# Z7_DDR3.net
KiCad netlist of a schematic drawn in Altium Designer
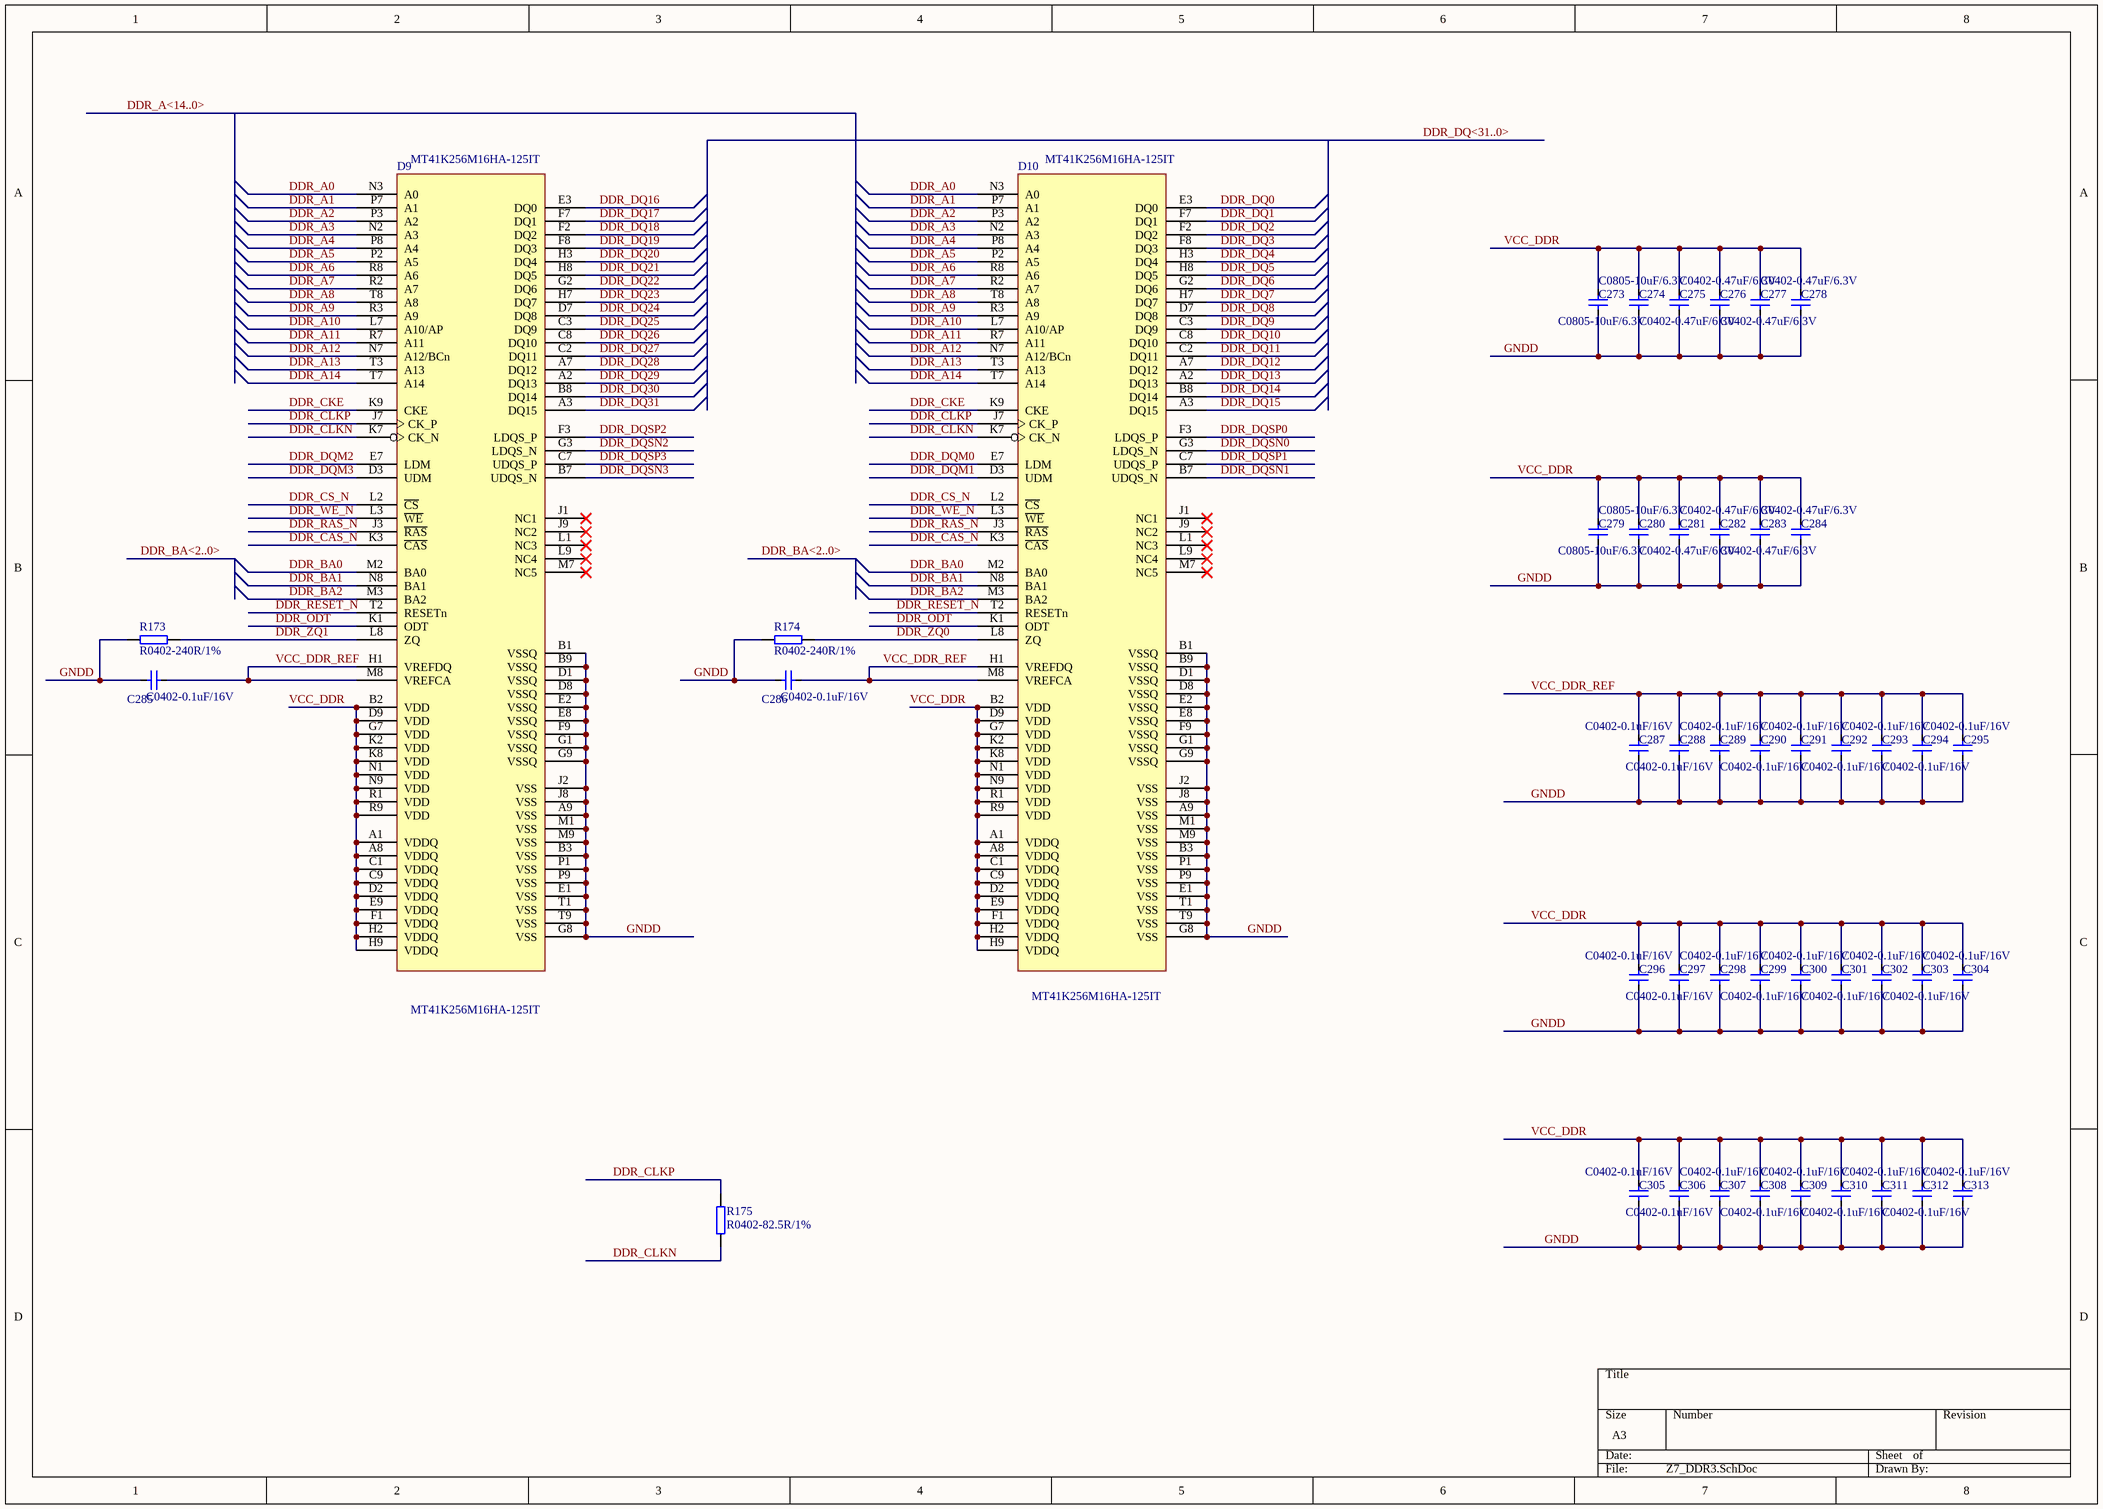
[diagram p0: Z7_DDR3.SchDoc]

(export (version "E")
  (design (tool "Eeschema 10.0.6"))
  (components
    (comp (ref "C273")
      (value "C0805-10uF/6.3V")
      (footprint "C0805")
      (fields (field (name "SCHEMATIC_PART") "CAP"))
      (libsource (lib "Database_Libs1") (part "CAP"))
    )
    (comp (ref "C274")
      (value "C0805-10uF/6.3V")
      (footprint "C0805")
      (fields (field (name "SCHEMATIC_PART") "CAP"))
      (libsource (lib "Database_Libs1") (part "CAP"))
    )
    (comp (ref "C275")
      (value "C0402-0.47uF/6.3V")
      (footprint "C0402")
      (description "X7R")
      (fields (field (name "SCHEMATIC_PART") "CAP") (field (name "MANUFACTURER") "SAMSUNG"))
      (libsource (lib "Database_Libs1") (part "CAP"))
    )
    (comp (ref "C276")
      (value "C0402-0.47uF/6.3V")
      (footprint "C0402")
      (description "X7R")
      (fields (field (name "SCHEMATIC_PART") "CAP") (field (name "MANUFACTURER") "SAMSUNG"))
      (libsource (lib "Database_Libs1") (part "CAP"))
    )
    (comp (ref "C277")
      (value "C0402-0.47uF/6.3V")
      (footprint "C0402")
      (description "X7R")
      (fields (field (name "SCHEMATIC_PART") "CAP") (field (name "MANUFACTURER") "SAMSUNG"))
      (libsource (lib "Database_Libs1") (part "CAP"))
    )
    (comp (ref "C278")
      (value "C0402-0.47uF/6.3V")
      (footprint "C0402")
      (description "X7R")
      (fields (field (name "SCHEMATIC_PART") "CAP") (field (name "MANUFACTURER") "SAMSUNG"))
      (libsource (lib "Database_Libs1") (part "CAP"))
    )
    (comp (ref "C279")
      (value "C0805-10uF/6.3V")
      (footprint "C0805")
      (fields (field (name "SCHEMATIC_PART") "CAP"))
      (libsource (lib "Database_Libs1") (part "CAP"))
    )
    (comp (ref "C280")
      (value "C0805-10uF/6.3V")
      (footprint "C0805")
      (fields (field (name "SCHEMATIC_PART") "CAP"))
      (libsource (lib "Database_Libs1") (part "CAP"))
    )
    (comp (ref "C281")
      (value "C0402-0.47uF/6.3V")
      (footprint "C0402")
      (description "X7R")
      (fields (field (name "SCHEMATIC_PART") "CAP") (field (name "MANUFACTURER") "SAMSUNG"))
      (libsource (lib "Database_Libs1") (part "CAP"))
    )
    (comp (ref "C282")
      (value "C0402-0.47uF/6.3V")
      (footprint "C0402")
      (description "X7R")
      (fields (field (name "SCHEMATIC_PART") "CAP") (field (name "MANUFACTURER") "SAMSUNG"))
      (libsource (lib "Database_Libs1") (part "CAP"))
    )
    (comp (ref "C283")
      (value "C0402-0.47uF/6.3V")
      (footprint "C0402")
      (description "X7R")
      (fields (field (name "SCHEMATIC_PART") "CAP") (field (name "MANUFACTURER") "SAMSUNG"))
      (libsource (lib "Database_Libs1") (part "CAP"))
    )
    (comp (ref "C284")
      (value "C0402-0.47uF/6.3V")
      (footprint "C0402")
      (description "X7R")
      (fields (field (name "SCHEMATIC_PART") "CAP") (field (name "MANUFACTURER") "SAMSUNG"))
      (libsource (lib "Database_Libs1") (part "CAP"))
    )
    (comp (ref "C285")
      (value "C0402-0.1uF/16V")
      (footprint "C0402")
      (description "X7R")
      (fields (field (name "SCHEMATIC_PART") "CAP") (field (name "MANUFACTURER") "SAMSUNG"))
      (libsource (lib "Database_Libs1") (part "CAP"))
    )
    (comp (ref "C286")
      (value "C0402-0.1uF/16V")
      (footprint "C0402")
      (description "X7R")
      (fields (field (name "SCHEMATIC_PART") "CAP") (field (name "MANUFACTURER") "SAMSUNG"))
      (libsource (lib "Database_Libs1") (part "CAP"))
    )
    (comp (ref "C287")
      (value "C0402-0.1uF/16V")
      (footprint "C0402")
      (description "X7R")
      (fields (field (name "SCHEMATIC_PART") "CAP") (field (name "MANUFACTURER") "SAMSUNG"))
      (libsource (lib "Database_Libs1") (part "CAP"))
    )
    (comp (ref "C288")
      (value "C0402-0.1uF/16V")
      (footprint "C0402")
      (description "X7R")
      (fields (field (name "SCHEMATIC_PART") "CAP") (field (name "MANUFACTURER") "SAMSUNG"))
      (libsource (lib "Database_Libs1") (part "CAP"))
    )
    (comp (ref "C289")
      (value "C0402-0.1uF/16V")
      (footprint "C0402")
      (description "X7R")
      (fields (field (name "SCHEMATIC_PART") "CAP") (field (name "MANUFACTURER") "SAMSUNG"))
      (libsource (lib "Database_Libs1") (part "CAP"))
    )
    (comp (ref "C290")
      (value "C0402-0.1uF/16V")
      (footprint "C0402")
      (description "X7R")
      (fields (field (name "SCHEMATIC_PART") "CAP") (field (name "MANUFACTURER") "SAMSUNG"))
      (libsource (lib "Database_Libs1") (part "CAP"))
    )
    (comp (ref "C291")
      (value "C0402-0.1uF/16V")
      (footprint "C0402")
      (description "X7R")
      (fields (field (name "SCHEMATIC_PART") "CAP") (field (name "MANUFACTURER") "SAMSUNG"))
      (libsource (lib "Database_Libs1") (part "CAP"))
    )
    (comp (ref "C292")
      (value "C0402-0.1uF/16V")
      (footprint "C0402")
      (description "X7R")
      (fields (field (name "SCHEMATIC_PART") "CAP") (field (name "MANUFACTURER") "SAMSUNG"))
      (libsource (lib "Database_Libs1") (part "CAP"))
    )
    (comp (ref "C293")
      (value "C0402-0.1uF/16V")
      (footprint "C0402")
      (description "X7R")
      (fields (field (name "SCHEMATIC_PART") "CAP") (field (name "MANUFACTURER") "SAMSUNG"))
      (libsource (lib "Database_Libs1") (part "CAP"))
    )
    (comp (ref "C294")
      (value "C0402-0.1uF/16V")
      (footprint "C0402")
      (description "X7R")
      (fields (field (name "SCHEMATIC_PART") "CAP") (field (name "MANUFACTURER") "SAMSUNG"))
      (libsource (lib "Database_Libs1") (part "CAP"))
    )
    (comp (ref "C295")
      (value "C0402-0.1uF/16V")
      (footprint "C0402")
      (description "X7R")
      (fields (field (name "SCHEMATIC_PART") "CAP") (field (name "MANUFACTURER") "SAMSUNG"))
      (libsource (lib "Database_Libs1") (part "CAP"))
    )
    (comp (ref "C296")
      (value "C0402-0.1uF/16V")
      (footprint "C0402")
      (description "X7R")
      (fields (field (name "SCHEMATIC_PART") "CAP") (field (name "MANUFACTURER") "SAMSUNG"))
      (libsource (lib "Database_Libs1") (part "CAP"))
    )
    (comp (ref "C297")
      (value "C0402-0.1uF/16V")
      (footprint "C0402")
      (description "X7R")
      (fields (field (name "SCHEMATIC_PART") "CAP") (field (name "MANUFACTURER") "SAMSUNG"))
      (libsource (lib "Database_Libs1") (part "CAP"))
    )
    (comp (ref "C298")
      (value "C0402-0.1uF/16V")
      (footprint "C0402")
      (description "X7R")
      (fields (field (name "SCHEMATIC_PART") "CAP") (field (name "MANUFACTURER") "SAMSUNG"))
      (libsource (lib "Database_Libs1") (part "CAP"))
    )
    (comp (ref "C299")
      (value "C0402-0.1uF/16V")
      (footprint "C0402")
      (description "X7R")
      (fields (field (name "SCHEMATIC_PART") "CAP") (field (name "MANUFACTURER") "SAMSUNG"))
      (libsource (lib "Database_Libs1") (part "CAP"))
    )
    (comp (ref "C300")
      (value "C0402-0.1uF/16V")
      (footprint "C0402")
      (description "X7R")
      (fields (field (name "SCHEMATIC_PART") "CAP") (field (name "MANUFACTURER") "SAMSUNG"))
      (libsource (lib "Database_Libs1") (part "CAP"))
    )
    (comp (ref "C301")
      (value "C0402-0.1uF/16V")
      (footprint "C0402")
      (description "X7R")
      (fields (field (name "SCHEMATIC_PART") "CAP") (field (name "MANUFACTURER") "SAMSUNG"))
      (libsource (lib "Database_Libs1") (part "CAP"))
    )
    (comp (ref "C302")
      (value "C0402-0.1uF/16V")
      (footprint "C0402")
      (description "X7R")
      (fields (field (name "SCHEMATIC_PART") "CAP") (field (name "MANUFACTURER") "SAMSUNG"))
      (libsource (lib "Database_Libs1") (part "CAP"))
    )
    (comp (ref "C303")
      (value "C0402-0.1uF/16V")
      (footprint "C0402")
      (description "X7R")
      (fields (field (name "SCHEMATIC_PART") "CAP") (field (name "MANUFACTURER") "SAMSUNG"))
      (libsource (lib "Database_Libs1") (part "CAP"))
    )
    (comp (ref "C304")
      (value "C0402-0.1uF/16V")
      (footprint "C0402")
      (description "X7R")
      (fields (field (name "SCHEMATIC_PART") "CAP") (field (name "MANUFACTURER") "SAMSUNG"))
      (libsource (lib "Database_Libs1") (part "CAP"))
    )
    (comp (ref "C305")
      (value "C0402-0.1uF/16V")
      (footprint "C0402")
      (description "X7R")
      (fields (field (name "SCHEMATIC_PART") "CAP") (field (name "MANUFACTURER") "SAMSUNG"))
      (libsource (lib "Database_Libs1") (part "CAP"))
    )
    (comp (ref "C306")
      (value "C0402-0.1uF/16V")
      (footprint "C0402")
      (description "X7R")
      (fields (field (name "SCHEMATIC_PART") "CAP") (field (name "MANUFACTURER") "SAMSUNG"))
      (libsource (lib "Database_Libs1") (part "CAP"))
    )
    (comp (ref "C307")
      (value "C0402-0.1uF/16V")
      (footprint "C0402")
      (description "X7R")
      (fields (field (name "SCHEMATIC_PART") "CAP") (field (name "MANUFACTURER") "SAMSUNG"))
      (libsource (lib "Database_Libs1") (part "CAP"))
    )
    (comp (ref "C308")
      (value "C0402-0.1uF/16V")
      (footprint "C0402")
      (description "X7R")
      (fields (field (name "SCHEMATIC_PART") "CAP") (field (name "MANUFACTURER") "SAMSUNG"))
      (libsource (lib "Database_Libs1") (part "CAP"))
    )
    (comp (ref "C309")
      (value "C0402-0.1uF/16V")
      (footprint "C0402")
      (description "X7R")
      (fields (field (name "SCHEMATIC_PART") "CAP") (field (name "MANUFACTURER") "SAMSUNG"))
      (libsource (lib "Database_Libs1") (part "CAP"))
    )
    (comp (ref "C310")
      (value "C0402-0.1uF/16V")
      (footprint "C0402")
      (description "X7R")
      (fields (field (name "SCHEMATIC_PART") "CAP") (field (name "MANUFACTURER") "SAMSUNG"))
      (libsource (lib "Database_Libs1") (part "CAP"))
    )
    (comp (ref "C311")
      (value "C0402-0.1uF/16V")
      (footprint "C0402")
      (description "X7R")
      (fields (field (name "SCHEMATIC_PART") "CAP") (field (name "MANUFACTURER") "SAMSUNG"))
      (libsource (lib "Database_Libs1") (part "CAP"))
    )
    (comp (ref "C312")
      (value "C0402-0.1uF/16V")
      (footprint "C0402")
      (description "X7R")
      (fields (field (name "SCHEMATIC_PART") "CAP") (field (name "MANUFACTURER") "SAMSUNG"))
      (libsource (lib "Database_Libs1") (part "CAP"))
    )
    (comp (ref "C313")
      (value "C0402-0.1uF/16V")
      (footprint "C0402")
      (description "X7R")
      (fields (field (name "SCHEMATIC_PART") "CAP") (field (name "MANUFACTURER") "SAMSUNG"))
      (libsource (lib "Database_Libs1") (part "CAP"))
    )
    (comp (ref "D9")
      (value "MT41K256M16HA-125IT")
      (footprint "BGA96C80P16X9_1400X900X120")
      (fields (field (name "PART_NUMBER") "MT41K256M16HA-125IT"))
      (libsource (lib "SCHLIB1") (part "MT41K256M16"))
    )
    (comp (ref "D10")
      (value "MT41K256M16HA-125IT")
      (footprint "BGA96C80P16X9_1400X900X120")
      (fields (field (name "PART_NUMBER") "MT41K256M16HA-125IT"))
      (libsource (lib "SCHLIB1") (part "MT41K256M16"))
    )
    (comp (ref "R173")
      (value "R0402-240R/1%")
      (footprint "R0402")
      (fields (field (name "SCHEMATIC_PART") "RES") (field (name "MANUFACTURER") "SAMSUNG"))
      (libsource (lib "Database_Libs1") (part "RES"))
    )
    (comp (ref "R174")
      (value "R0402-240R/1%")
      (footprint "R0402")
      (fields (field (name "SCHEMATIC_PART") "RES") (field (name "MANUFACTURER") "SAMSUNG"))
      (libsource (lib "Database_Libs1") (part "RES"))
    )
    (comp (ref "R175")
      (value "R0402-82.5R/1%")
      (footprint "R0402")
      (fields (field (name "SCHEMATIC_PART") "RES") (field (name "MANUFACTURER") "SAMSUNG"))
      (libsource (lib "Database_Libs1") (part "RES"))
    )
  )
  (nets
    (net (code "4") (name "/DDR_A0") (class "Default")
      (node (ref "D10") (pin "N3") (pinfunction "A0_N3") (pintype "passive"))
      (node (ref "D9") (pin "N3") (pinfunction "A0_N3") (pintype "passive"))
    )
    (net (code "5") (name "/DDR_A1") (class "Default")
      (node (ref "D10") (pin "P7") (pinfunction "A1_P7") (pintype "passive"))
      (node (ref "D9") (pin "P7") (pinfunction "A1_P7") (pintype "passive"))
    )
    (net (code "6") (name "/DDR_A2") (class "Default")
      (node (ref "D10") (pin "P3") (pinfunction "A2_P3") (pintype "passive"))
      (node (ref "D9") (pin "P3") (pinfunction "A2_P3") (pintype "passive"))
    )
    (net (code "7") (name "/DDR_A3") (class "Default")
      (node (ref "D10") (pin "N2") (pinfunction "A3_N2") (pintype "passive"))
      (node (ref "D9") (pin "N2") (pinfunction "A3_N2") (pintype "passive"))
    )
    (net (code "8") (name "/DDR_A4") (class "Default")
      (node (ref "D10") (pin "P8") (pinfunction "A4_P8") (pintype "passive"))
      (node (ref "D9") (pin "P8") (pinfunction "A4_P8") (pintype "passive"))
    )
    (net (code "9") (name "/DDR_A5") (class "Default")
      (node (ref "D10") (pin "P2") (pinfunction "A5_P2") (pintype "passive"))
      (node (ref "D9") (pin "P2") (pinfunction "A5_P2") (pintype "passive"))
    )
    (net (code "10") (name "/DDR_A6") (class "Default")
      (node (ref "D10") (pin "R8") (pinfunction "A6_R8") (pintype "passive"))
      (node (ref "D9") (pin "R8") (pinfunction "A6_R8") (pintype "passive"))
    )
    (net (code "11") (name "/DDR_A7") (class "Default")
      (node (ref "D10") (pin "R2") (pinfunction "A7_R2") (pintype "passive"))
      (node (ref "D9") (pin "R2") (pinfunction "A7_R2") (pintype "passive"))
    )
    (net (code "12") (name "/DDR_A8") (class "Default")
      (node (ref "D10") (pin "T8") (pinfunction "A8_T8") (pintype "passive"))
      (node (ref "D9") (pin "T8") (pinfunction "A8_T8") (pintype "passive"))
    )
    (net (code "13") (name "/DDR_A9") (class "Default")
      (node (ref "D10") (pin "R3") (pinfunction "A9_R3") (pintype "passive"))
      (node (ref "D9") (pin "R3") (pinfunction "A9_R3") (pintype "passive"))
    )
    (net (code "14") (name "/DDR_A10") (class "Default")
      (node (ref "D10") (pin "L7") (pinfunction "A10/AP_L7") (pintype "passive"))
      (node (ref "D9") (pin "L7") (pinfunction "A10/AP_L7") (pintype "passive"))
    )
    (net (code "15") (name "/DDR_A11") (class "Default")
      (node (ref "D10") (pin "R7") (pinfunction "A11_R7") (pintype "passive"))
      (node (ref "D9") (pin "R7") (pinfunction "A11_R7") (pintype "passive"))
    )
    (net (code "16") (name "/DDR_A12") (class "Default")
      (node (ref "D10") (pin "N7") (pinfunction "A12/BCn_N7") (pintype "passive"))
      (node (ref "D9") (pin "N7") (pinfunction "A12/BCn_N7") (pintype "passive"))
    )
    (net (code "17") (name "/DDR_A13") (class "Default")
      (node (ref "D10") (pin "T3") (pinfunction "A13_T3") (pintype "passive"))
      (node (ref "D9") (pin "T3") (pinfunction "A13_T3") (pintype "passive"))
    )
    (net (code "18") (name "/DDR_A14") (class "Default")
      (node (ref "D10") (pin "T7") (pinfunction "A14_T7") (pintype "passive"))
      (node (ref "D9") (pin "T7") (pinfunction "A14_T7") (pintype "passive"))
    )
    (net (code "19") (name "/DDR_BA0") (class "Default")
      (node (ref "D10") (pin "M2") (pinfunction "BA0_M2") (pintype "passive"))
      (node (ref "D9") (pin "M2") (pinfunction "BA0_M2") (pintype "passive"))
    )
    (net (code "20") (name "/DDR_BA1") (class "Default")
      (node (ref "D10") (pin "N8") (pinfunction "BA1_N8") (pintype "passive"))
      (node (ref "D9") (pin "N8") (pinfunction "BA1_N8") (pintype "passive"))
    )
    (net (code "21") (name "/DDR_BA2") (class "Default")
      (node (ref "D10") (pin "M3") (pinfunction "BA2_M3") (pintype "passive"))
      (node (ref "D9") (pin "M3") (pinfunction "BA2_M3") (pintype "passive"))
    )
    (net (code "22") (name "/DDR_CAS_N") (class "Default")
      (node (ref "D10") (pin "K3") (pinfunction "~{CAS}_K3") (pintype "passive"))
      (node (ref "D9") (pin "K3") (pinfunction "~{CAS}_K3") (pintype "passive"))
    )
    (net (code "23") (name "/DDR_CKE") (class "Default")
      (node (ref "D10") (pin "K9") (pinfunction "CKE_K9") (pintype "passive"))
      (node (ref "D9") (pin "K9") (pinfunction "CKE_K9") (pintype "passive"))
    )
    (net (code "24") (name "/DDR_CLKN") (class "Default")
      (node (ref "D10") (pin "K7") (pinfunction "CK_N_K7") (pintype "passive"))
      (node (ref "D9") (pin "K7") (pinfunction "CK_N_K7") (pintype "passive"))
      (node (ref "R175") (pin "1") (pintype "passive"))
    )
    (net (code "25") (name "/DDR_CLKP") (class "Default")
      (node (ref "D10") (pin "J7") (pinfunction "CK_P_J7") (pintype "passive"))
      (node (ref "D9") (pin "J7") (pinfunction "CK_P_J7") (pintype "passive"))
      (node (ref "R175") (pin "2") (pintype "passive"))
    )
    (net (code "26") (name "/DDR_CS_N") (class "Default")
      (node (ref "D10") (pin "L2") (pinfunction "~{CS}_L2") (pintype "passive"))
      (node (ref "D9") (pin "L2") (pinfunction "~{CS}_L2") (pintype "passive"))
    )
    (net (code "27") (name "/DDR_DQ0") (class "Default")
      (node (ref "D10") (pin "E3") (pinfunction "DQ0_E3") (pintype "passive"))
    )
    (net (code "28") (name "/DDR_DQ1") (class "Default")
      (node (ref "D10") (pin "F7") (pinfunction "DQ1_F7") (pintype "passive"))
    )
    (net (code "29") (name "/DDR_DQ2") (class "Default")
      (node (ref "D10") (pin "F2") (pinfunction "DQ2_F2") (pintype "passive"))
    )
    (net (code "30") (name "/DDR_DQ3") (class "Default")
      (node (ref "D10") (pin "F8") (pinfunction "DQ3_F8") (pintype "passive"))
    )
    (net (code "31") (name "/DDR_DQ4") (class "Default")
      (node (ref "D10") (pin "H3") (pinfunction "DQ4_H3") (pintype "passive"))
    )
    (net (code "32") (name "/DDR_DQ5") (class "Default")
      (node (ref "D10") (pin "H8") (pinfunction "DQ5_H8") (pintype "passive"))
    )
    (net (code "33") (name "/DDR_DQ6") (class "Default")
      (node (ref "D10") (pin "G2") (pinfunction "DQ6_G2") (pintype "passive"))
    )
    (net (code "34") (name "/DDR_DQ7") (class "Default")
      (node (ref "D10") (pin "H7") (pinfunction "DQ7_H7") (pintype "passive"))
    )
    (net (code "35") (name "/DDR_DQ8") (class "Default")
      (node (ref "D10") (pin "D7") (pinfunction "DQ8_D7") (pintype "passive"))
    )
    (net (code "36") (name "/DDR_DQ9") (class "Default")
      (node (ref "D10") (pin "C3") (pinfunction "DQ9_C3") (pintype "passive"))
    )
    (net (code "37") (name "/DDR_DQ10") (class "Default")
      (node (ref "D10") (pin "C8") (pinfunction "DQ10_C8") (pintype "passive"))
    )
    (net (code "38") (name "/DDR_DQ11") (class "Default")
      (node (ref "D10") (pin "C2") (pinfunction "DQ11_C2") (pintype "passive"))
    )
    (net (code "39") (name "/DDR_DQ12") (class "Default")
      (node (ref "D10") (pin "A7") (pinfunction "DQ12_A7") (pintype "passive"))
    )
    (net (code "40") (name "/DDR_DQ13") (class "Default")
      (node (ref "D10") (pin "A2") (pinfunction "DQ13_A2") (pintype "passive"))
    )
    (net (code "41") (name "/DDR_DQ14") (class "Default")
      (node (ref "D10") (pin "B8") (pinfunction "DQ14_B8") (pintype "passive"))
    )
    (net (code "42") (name "/DDR_DQ15") (class "Default")
      (node (ref "D10") (pin "A3") (pinfunction "DQ15_A3") (pintype "passive"))
    )
    (net (code "43") (name "/DDR_DQ16") (class "Default")
      (node (ref "D9") (pin "E3") (pinfunction "DQ0_E3") (pintype "passive"))
    )
    (net (code "44") (name "/DDR_DQ17") (class "Default")
      (node (ref "D9") (pin "F7") (pinfunction "DQ1_F7") (pintype "passive"))
    )
    (net (code "45") (name "/DDR_DQ18") (class "Default")
      (node (ref "D9") (pin "F2") (pinfunction "DQ2_F2") (pintype "passive"))
    )
    (net (code "46") (name "/DDR_DQ19") (class "Default")
      (node (ref "D9") (pin "F8") (pinfunction "DQ3_F8") (pintype "passive"))
    )
    (net (code "47") (name "/DDR_DQ20") (class "Default")
      (node (ref "D9") (pin "H3") (pinfunction "DQ4_H3") (pintype "passive"))
    )
    (net (code "48") (name "/DDR_DQ21") (class "Default")
      (node (ref "D9") (pin "H8") (pinfunction "DQ5_H8") (pintype "passive"))
    )
    (net (code "49") (name "/DDR_DQ22") (class "Default")
      (node (ref "D9") (pin "G2") (pinfunction "DQ6_G2") (pintype "passive"))
    )
    (net (code "50") (name "/DDR_DQ23") (class "Default")
      (node (ref "D9") (pin "H7") (pinfunction "DQ7_H7") (pintype "passive"))
    )
    (net (code "51") (name "/DDR_DQ24") (class "Default")
      (node (ref "D9") (pin "D7") (pinfunction "DQ8_D7") (pintype "passive"))
    )
    (net (code "52") (name "/DDR_DQ25") (class "Default")
      (node (ref "D9") (pin "C3") (pinfunction "DQ9_C3") (pintype "passive"))
    )
    (net (code "53") (name "/DDR_DQ26") (class "Default")
      (node (ref "D9") (pin "C8") (pinfunction "DQ10_C8") (pintype "passive"))
    )
    (net (code "54") (name "/DDR_DQ27") (class "Default")
      (node (ref "D9") (pin "C2") (pinfunction "DQ11_C2") (pintype "passive"))
    )
    (net (code "55") (name "/DDR_DQ28") (class "Default")
      (node (ref "D9") (pin "A7") (pinfunction "DQ12_A7") (pintype "passive"))
    )
    (net (code "56") (name "/DDR_DQ29") (class "Default")
      (node (ref "D9") (pin "A2") (pinfunction "DQ13_A2") (pintype "passive"))
    )
    (net (code "57") (name "/DDR_DQ30") (class "Default")
      (node (ref "D9") (pin "B8") (pinfunction "DQ14_B8") (pintype "passive"))
    )
    (net (code "58") (name "/DDR_DQ31") (class "Default")
      (node (ref "D9") (pin "A3") (pinfunction "DQ15_A3") (pintype "passive"))
    )
    (net (code "59") (name "/DDR_DQM0") (class "Default")
      (node (ref "D10") (pin "E7") (pinfunction "LDM_E7") (pintype "passive"))
    )
    (net (code "60") (name "/DDR_DQM1") (class "Default")
      (node (ref "D10") (pin "D3") (pinfunction "UDM_D3") (pintype "passive"))
    )
    (net (code "61") (name "/DDR_DQM2") (class "Default")
      (node (ref "D9") (pin "E7") (pinfunction "LDM_E7") (pintype "passive"))
    )
    (net (code "62") (name "/DDR_DQM3") (class "Default")
      (node (ref "D9") (pin "D3") (pinfunction "UDM_D3") (pintype "passive"))
    )
    (net (code "63") (name "/DDR_DQSN0") (class "Default")
      (node (ref "D10") (pin "G3") (pinfunction "LDQS_N_G3") (pintype "passive"))
    )
    (net (code "64") (name "/DDR_DQSN1") (class "Default")
      (node (ref "D10") (pin "B7") (pinfunction "UDQS_N_B7") (pintype "passive"))
    )
    (net (code "65") (name "/DDR_DQSN2") (class "Default")
      (node (ref "D9") (pin "G3") (pinfunction "LDQS_N_G3") (pintype "passive"))
    )
    (net (code "66") (name "/DDR_DQSN3") (class "Default")
      (node (ref "D9") (pin "B7") (pinfunction "UDQS_N_B7") (pintype "passive"))
    )
    (net (code "67") (name "/DDR_DQSP0") (class "Default")
      (node (ref "D10") (pin "F3") (pinfunction "LDQS_P_F3") (pintype "passive"))
    )
    (net (code "68") (name "/DDR_DQSP1") (class "Default")
      (node (ref "D10") (pin "C7") (pinfunction "UDQS_P_C7") (pintype "passive"))
    )
    (net (code "69") (name "/DDR_DQSP2") (class "Default")
      (node (ref "D9") (pin "F3") (pinfunction "LDQS_P_F3") (pintype "passive"))
    )
    (net (code "70") (name "/DDR_DQSP3") (class "Default")
      (node (ref "D9") (pin "C7") (pinfunction "UDQS_P_C7") (pintype "passive"))
    )
    (net (code "71") (name "/DDR_ODT") (class "Default")
      (node (ref "D10") (pin "K1") (pinfunction "ODT_K1") (pintype "passive"))
      (node (ref "D9") (pin "K1") (pinfunction "ODT_K1") (pintype "passive"))
    )
    (net (code "72") (name "/DDR_RAS_N") (class "Default")
      (node (ref "D10") (pin "J3") (pinfunction "~{RAS}_J3") (pintype "passive"))
      (node (ref "D9") (pin "J3") (pinfunction "~{RAS}_J3") (pintype "passive"))
    )
    (net (code "73") (name "/DDR_RESET_N") (class "Default")
      (node (ref "D10") (pin "T2") (pinfunction "RESETn_T2") (pintype "passive"))
      (node (ref "D9") (pin "T2") (pinfunction "RESETn_T2") (pintype "passive"))
    )
    (net (code "74") (name "/DDR_WE_N") (class "Default")
      (node (ref "D10") (pin "L3") (pinfunction "~{WE}_L3") (pintype "passive"))
      (node (ref "D9") (pin "L3") (pinfunction "~{WE}_L3") (pintype "passive"))
    )
    (net (code "75") (name "/DDR_ZQ0") (class "Default")
      (node (ref "D10") (pin "L8") (pinfunction "ZQ_L8") (pintype "passive"))
      (node (ref "R174") (pin "1") (pintype "passive"))
    )
    (net (code "76") (name "/DDR_ZQ1") (class "Default")
      (node (ref "D9") (pin "L8") (pinfunction "ZQ_L8") (pintype "passive"))
      (node (ref "R173") (pin "1") (pintype "passive"))
    )
    (net (code "77") (name "/GNDD") (class "Default")
      (node (ref "C273") (pin "2") (pinfunction "2_2") (pintype "passive"))
      (node (ref "C274") (pin "2") (pinfunction "2_2") (pintype "passive"))
      (node (ref "C275") (pin "2") (pinfunction "2_2") (pintype "passive"))
      (node (ref "C276") (pin "2") (pinfunction "2_2") (pintype "passive"))
      (node (ref "C277") (pin "2") (pinfunction "2_2") (pintype "passive"))
      (node (ref "C278") (pin "2") (pinfunction "2_2") (pintype "passive"))
      (node (ref "C279") (pin "2") (pinfunction "2_2") (pintype "passive"))
      (node (ref "C280") (pin "2") (pinfunction "2_2") (pintype "passive"))
      (node (ref "C281") (pin "2") (pinfunction "2_2") (pintype "passive"))
      (node (ref "C282") (pin "2") (pinfunction "2_2") (pintype "passive"))
      (node (ref "C283") (pin "2") (pinfunction "2_2") (pintype "passive"))
      (node (ref "C284") (pin "2") (pinfunction "2_2") (pintype "passive"))
      (node (ref "C285") (pin "1") (pinfunction "1_1") (pintype "passive"))
      (node (ref "C286") (pin "1") (pinfunction "1_1") (pintype "passive"))
      (node (ref "C287") (pin "2") (pinfunction "2_2") (pintype "passive"))
      (node (ref "C288") (pin "2") (pinfunction "2_2") (pintype "passive"))
      (node (ref "C289") (pin "2") (pinfunction "2_2") (pintype "passive"))
      (node (ref "C290") (pin "2") (pinfunction "2_2") (pintype "passive"))
      (node (ref "C291") (pin "2") (pinfunction "2_2") (pintype "passive"))
      (node (ref "C292") (pin "2") (pinfunction "2_2") (pintype "passive"))
      (node (ref "C293") (pin "2") (pinfunction "2_2") (pintype "passive"))
      (node (ref "C294") (pin "2") (pinfunction "2_2") (pintype "passive"))
      (node (ref "C295") (pin "2") (pinfunction "2_2") (pintype "passive"))
      (node (ref "C296") (pin "2") (pinfunction "2_2") (pintype "passive"))
      (node (ref "C297") (pin "2") (pinfunction "2_2") (pintype "passive"))
      (node (ref "C298") (pin "2") (pinfunction "2_2") (pintype "passive"))
      (node (ref "C299") (pin "2") (pinfunction "2_2") (pintype "passive"))
      (node (ref "C300") (pin "2") (pinfunction "2_2") (pintype "passive"))
      (node (ref "C301") (pin "2") (pinfunction "2_2") (pintype "passive"))
      (node (ref "C302") (pin "2") (pinfunction "2_2") (pintype "passive"))
      (node (ref "C303") (pin "2") (pinfunction "2_2") (pintype "passive"))
      (node (ref "C304") (pin "2") (pinfunction "2_2") (pintype "passive"))
      (node (ref "C305") (pin "2") (pinfunction "2_2") (pintype "passive"))
      (node (ref "C306") (pin "2") (pinfunction "2_2") (pintype "passive"))
      (node (ref "C307") (pin "2") (pinfunction "2_2") (pintype "passive"))
      (node (ref "C308") (pin "2") (pinfunction "2_2") (pintype "passive"))
      (node (ref "C309") (pin "2") (pinfunction "2_2") (pintype "passive"))
      (node (ref "C310") (pin "2") (pinfunction "2_2") (pintype "passive"))
      (node (ref "C311") (pin "2") (pinfunction "2_2") (pintype "passive"))
      (node (ref "C312") (pin "2") (pinfunction "2_2") (pintype "passive"))
      (node (ref "C313") (pin "2") (pinfunction "2_2") (pintype "passive"))
      (node (ref "D10") (pin "A9") (pinfunction "VSS_A9") (pintype "passive"))
      (node (ref "D10") (pin "B1") (pinfunction "VSSQ_B1") (pintype "passive"))
      (node (ref "D10") (pin "B3") (pinfunction "VSS_B3") (pintype "passive"))
      (node (ref "D10") (pin "B9") (pinfunction "VSSQ_B9") (pintype "passive"))
      (node (ref "D10") (pin "D1") (pinfunction "VSSQ_D1") (pintype "passive"))
      (node (ref "D10") (pin "D8") (pinfunction "VSSQ_D8") (pintype "passive"))
      (node (ref "D10") (pin "E1") (pinfunction "VSS_E1") (pintype "passive"))
      (node (ref "D10") (pin "E2") (pinfunction "VSSQ_E2") (pintype "passive"))
      (node (ref "D10") (pin "E8") (pinfunction "VSSQ_E8") (pintype "passive"))
      (node (ref "D10") (pin "F9") (pinfunction "VSSQ_F9") (pintype "passive"))
      (node (ref "D10") (pin "G1") (pinfunction "VSSQ_G1") (pintype "passive"))
      (node (ref "D10") (pin "G8") (pinfunction "VSS_G8") (pintype "passive"))
      (node (ref "D10") (pin "G9") (pinfunction "VSSQ_G9") (pintype "passive"))
      (node (ref "D10") (pin "J2") (pinfunction "VSS_J2") (pintype "passive"))
      (node (ref "D10") (pin "J8") (pinfunction "VSS_J8") (pintype "passive"))
      (node (ref "D10") (pin "M1") (pinfunction "VSS_M1") (pintype "passive"))
      (node (ref "D10") (pin "M9") (pinfunction "VSS_M9") (pintype "passive"))
      (node (ref "D10") (pin "P1") (pinfunction "VSS_P1") (pintype "passive"))
      (node (ref "D10") (pin "P9") (pinfunction "VSS_P9") (pintype "passive"))
      (node (ref "D10") (pin "T1") (pinfunction "VSS_T1") (pintype "passive"))
      (node (ref "D10") (pin "T9") (pinfunction "VSS_T9") (pintype "passive"))
      (node (ref "D9") (pin "A9") (pinfunction "VSS_A9") (pintype "passive"))
      (node (ref "D9") (pin "B1") (pinfunction "VSSQ_B1") (pintype "passive"))
      (node (ref "D9") (pin "B3") (pinfunction "VSS_B3") (pintype "passive"))
      (node (ref "D9") (pin "B9") (pinfunction "VSSQ_B9") (pintype "passive"))
      (node (ref "D9") (pin "D1") (pinfunction "VSSQ_D1") (pintype "passive"))
      (node (ref "D9") (pin "D8") (pinfunction "VSSQ_D8") (pintype "passive"))
      (node (ref "D9") (pin "E1") (pinfunction "VSS_E1") (pintype "passive"))
      (node (ref "D9") (pin "E2") (pinfunction "VSSQ_E2") (pintype "passive"))
      (node (ref "D9") (pin "E8") (pinfunction "VSSQ_E8") (pintype "passive"))
      (node (ref "D9") (pin "F9") (pinfunction "VSSQ_F9") (pintype "passive"))
      (node (ref "D9") (pin "G1") (pinfunction "VSSQ_G1") (pintype "passive"))
      (node (ref "D9") (pin "G8") (pinfunction "VSS_G8") (pintype "passive"))
      (node (ref "D9") (pin "G9") (pinfunction "VSSQ_G9") (pintype "passive"))
      (node (ref "D9") (pin "J2") (pinfunction "VSS_J2") (pintype "passive"))
      (node (ref "D9") (pin "J8") (pinfunction "VSS_J8") (pintype "passive"))
      (node (ref "D9") (pin "M1") (pinfunction "VSS_M1") (pintype "passive"))
      (node (ref "D9") (pin "M9") (pinfunction "VSS_M9") (pintype "passive"))
      (node (ref "D9") (pin "P1") (pinfunction "VSS_P1") (pintype "passive"))
      (node (ref "D9") (pin "P9") (pinfunction "VSS_P9") (pintype "passive"))
      (node (ref "D9") (pin "T1") (pinfunction "VSS_T1") (pintype "passive"))
      (node (ref "D9") (pin "T9") (pinfunction "VSS_T9") (pintype "passive"))
      (node (ref "R173") (pin "2") (pintype "passive"))
      (node (ref "R174") (pin "2") (pintype "passive"))
    )
    (net (code "78") (name "/VCC_DDR") (class "Default")
      (node (ref "C273") (pin "1") (pinfunction "1_1") (pintype "passive"))
      (node (ref "C274") (pin "1") (pinfunction "1_1") (pintype "passive"))
      (node (ref "C275") (pin "1") (pinfunction "1_1") (pintype "passive"))
      (node (ref "C276") (pin "1") (pinfunction "1_1") (pintype "passive"))
      (node (ref "C277") (pin "1") (pinfunction "1_1") (pintype "passive"))
      (node (ref "C278") (pin "1") (pinfunction "1_1") (pintype "passive"))
      (node (ref "C279") (pin "1") (pinfunction "1_1") (pintype "passive"))
      (node (ref "C280") (pin "1") (pinfunction "1_1") (pintype "passive"))
      (node (ref "C281") (pin "1") (pinfunction "1_1") (pintype "passive"))
      (node (ref "C282") (pin "1") (pinfunction "1_1") (pintype "passive"))
      (node (ref "C283") (pin "1") (pinfunction "1_1") (pintype "passive"))
      (node (ref "C284") (pin "1") (pinfunction "1_1") (pintype "passive"))
      (node (ref "C296") (pin "1") (pinfunction "1_1") (pintype "passive"))
      (node (ref "C297") (pin "1") (pinfunction "1_1") (pintype "passive"))
      (node (ref "C298") (pin "1") (pinfunction "1_1") (pintype "passive"))
      (node (ref "C299") (pin "1") (pinfunction "1_1") (pintype "passive"))
      (node (ref "C300") (pin "1") (pinfunction "1_1") (pintype "passive"))
      (node (ref "C301") (pin "1") (pinfunction "1_1") (pintype "passive"))
      (node (ref "C302") (pin "1") (pinfunction "1_1") (pintype "passive"))
      (node (ref "C303") (pin "1") (pinfunction "1_1") (pintype "passive"))
      (node (ref "C304") (pin "1") (pinfunction "1_1") (pintype "passive"))
      (node (ref "C305") (pin "1") (pinfunction "1_1") (pintype "passive"))
      (node (ref "C306") (pin "1") (pinfunction "1_1") (pintype "passive"))
      (node (ref "C307") (pin "1") (pinfunction "1_1") (pintype "passive"))
      (node (ref "C308") (pin "1") (pinfunction "1_1") (pintype "passive"))
      (node (ref "C309") (pin "1") (pinfunction "1_1") (pintype "passive"))
      (node (ref "C310") (pin "1") (pinfunction "1_1") (pintype "passive"))
      (node (ref "C311") (pin "1") (pinfunction "1_1") (pintype "passive"))
      (node (ref "C312") (pin "1") (pinfunction "1_1") (pintype "passive"))
      (node (ref "C313") (pin "1") (pinfunction "1_1") (pintype "passive"))
      (node (ref "D10") (pin "A1") (pinfunction "VDDQ_A1") (pintype "passive"))
      (node (ref "D10") (pin "A8") (pinfunction "VDDQ_A8") (pintype "passive"))
      (node (ref "D10") (pin "B2") (pinfunction "VDD_B2") (pintype "passive"))
      (node (ref "D10") (pin "C1") (pinfunction "VDDQ_C1") (pintype "passive"))
      (node (ref "D10") (pin "C9") (pinfunction "VDDQ_C9") (pintype "passive"))
      (node (ref "D10") (pin "D2") (pinfunction "VDDQ_D2") (pintype "passive"))
      (node (ref "D10") (pin "D9") (pinfunction "VDD_D9") (pintype "passive"))
      (node (ref "D10") (pin "E9") (pinfunction "VDDQ_E9") (pintype "passive"))
      (node (ref "D10") (pin "F1") (pinfunction "VDDQ_F1") (pintype "passive"))
      (node (ref "D10") (pin "G7") (pinfunction "VDD_G7") (pintype "passive"))
      (node (ref "D10") (pin "H2") (pinfunction "VDDQ_H2") (pintype "passive"))
      (node (ref "D10") (pin "H9") (pinfunction "VDDQ_H9") (pintype "passive"))
      (node (ref "D10") (pin "K2") (pinfunction "VDD_K2") (pintype "passive"))
      (node (ref "D10") (pin "K8") (pinfunction "VDD_K8") (pintype "passive"))
      (node (ref "D10") (pin "N1") (pinfunction "VDD_N1") (pintype "passive"))
      (node (ref "D10") (pin "N9") (pinfunction "VDD_N9") (pintype "passive"))
      (node (ref "D10") (pin "R1") (pinfunction "VDD_R1") (pintype "passive"))
      (node (ref "D10") (pin "R9") (pinfunction "VDD_R9") (pintype "passive"))
      (node (ref "D9") (pin "A1") (pinfunction "VDDQ_A1") (pintype "passive"))
      (node (ref "D9") (pin "A8") (pinfunction "VDDQ_A8") (pintype "passive"))
      (node (ref "D9") (pin "B2") (pinfunction "VDD_B2") (pintype "passive"))
      (node (ref "D9") (pin "C1") (pinfunction "VDDQ_C1") (pintype "passive"))
      (node (ref "D9") (pin "C9") (pinfunction "VDDQ_C9") (pintype "passive"))
      (node (ref "D9") (pin "D2") (pinfunction "VDDQ_D2") (pintype "passive"))
      (node (ref "D9") (pin "D9") (pinfunction "VDD_D9") (pintype "passive"))
      (node (ref "D9") (pin "E9") (pinfunction "VDDQ_E9") (pintype "passive"))
      (node (ref "D9") (pin "F1") (pinfunction "VDDQ_F1") (pintype "passive"))
      (node (ref "D9") (pin "G7") (pinfunction "VDD_G7") (pintype "passive"))
      (node (ref "D9") (pin "H2") (pinfunction "VDDQ_H2") (pintype "passive"))
      (node (ref "D9") (pin "H9") (pinfunction "VDDQ_H9") (pintype "passive"))
      (node (ref "D9") (pin "K2") (pinfunction "VDD_K2") (pintype "passive"))
      (node (ref "D9") (pin "K8") (pinfunction "VDD_K8") (pintype "passive"))
      (node (ref "D9") (pin "N1") (pinfunction "VDD_N1") (pintype "passive"))
      (node (ref "D9") (pin "N9") (pinfunction "VDD_N9") (pintype "passive"))
      (node (ref "D9") (pin "R1") (pinfunction "VDD_R1") (pintype "passive"))
      (node (ref "D9") (pin "R9") (pinfunction "VDD_R9") (pintype "passive"))
    )
    (net (code "79") (name "/VCC_DDR_REF") (class "Default")
      (node (ref "C285") (pin "2") (pinfunction "2_2") (pintype "passive"))
      (node (ref "C286") (pin "2") (pinfunction "2_2") (pintype "passive"))
      (node (ref "C287") (pin "1") (pinfunction "1_1") (pintype "passive"))
      (node (ref "C288") (pin "1") (pinfunction "1_1") (pintype "passive"))
      (node (ref "C289") (pin "1") (pinfunction "1_1") (pintype "passive"))
      (node (ref "C290") (pin "1") (pinfunction "1_1") (pintype "passive"))
      (node (ref "C291") (pin "1") (pinfunction "1_1") (pintype "passive"))
      (node (ref "C292") (pin "1") (pinfunction "1_1") (pintype "passive"))
      (node (ref "C293") (pin "1") (pinfunction "1_1") (pintype "passive"))
      (node (ref "C294") (pin "1") (pinfunction "1_1") (pintype "passive"))
      (node (ref "C295") (pin "1") (pinfunction "1_1") (pintype "passive"))
      (node (ref "D10") (pin "H1") (pinfunction "VREFDQ_H1") (pintype "passive"))
      (node (ref "D10") (pin "M8") (pinfunction "VREFCA_M8") (pintype "passive"))
      (node (ref "D9") (pin "H1") (pinfunction "VREFDQ_H1") (pintype "passive"))
      (node (ref "D9") (pin "M8") (pinfunction "VREFCA_M8") (pintype "passive"))
    )
    (net (code "83") (name "unconnected-(D9-NC1-PadJ1)") (class "Default")
      (node (ref "D9") (pin "J1") (pinfunction "NC1_J1") (pintype "passive+no_connect"))
    )
    (net (code "84") (name "unconnected-(D9-NC2-PadJ9)") (class "Default")
      (node (ref "D9") (pin "J9") (pinfunction "NC2_J9") (pintype "passive+no_connect"))
    )
    (net (code "85") (name "unconnected-(D9-NC3-PadL1)") (class "Default")
      (node (ref "D9") (pin "L1") (pinfunction "NC3_L1") (pintype "passive+no_connect"))
    )
    (net (code "86") (name "unconnected-(D9-NC4-PadL9)") (class "Default")
      (node (ref "D9") (pin "L9") (pinfunction "NC4_L9") (pintype "passive+no_connect"))
    )
    (net (code "87") (name "unconnected-(D9-NC5-PadM7)") (class "Default")
      (node (ref "D9") (pin "M7") (pinfunction "NC5_M7") (pintype "passive+no_connect"))
    )
    (net (code "88") (name "unconnected-(D10-NC1-PadJ1)") (class "Default")
      (node (ref "D10") (pin "J1") (pinfunction "NC1_J1") (pintype "passive+no_connect"))
    )
    (net (code "89") (name "unconnected-(D10-NC2-PadJ9)") (class "Default")
      (node (ref "D10") (pin "J9") (pinfunction "NC2_J9") (pintype "passive+no_connect"))
    )
    (net (code "90") (name "unconnected-(D10-NC3-PadL1)") (class "Default")
      (node (ref "D10") (pin "L1") (pinfunction "NC3_L1") (pintype "passive+no_connect"))
    )
    (net (code "91") (name "unconnected-(D10-NC4-PadL9)") (class "Default")
      (node (ref "D10") (pin "L9") (pinfunction "NC4_L9") (pintype "passive+no_connect"))
    )
    (net (code "92") (name "unconnected-(D10-NC5-PadM7)") (class "Default")
      (node (ref "D10") (pin "M7") (pinfunction "NC5_M7") (pintype "passive+no_connect"))
    )
  )
)
